# Sensors.net
KiCad netlist of a schematic drawn in Altium Designer
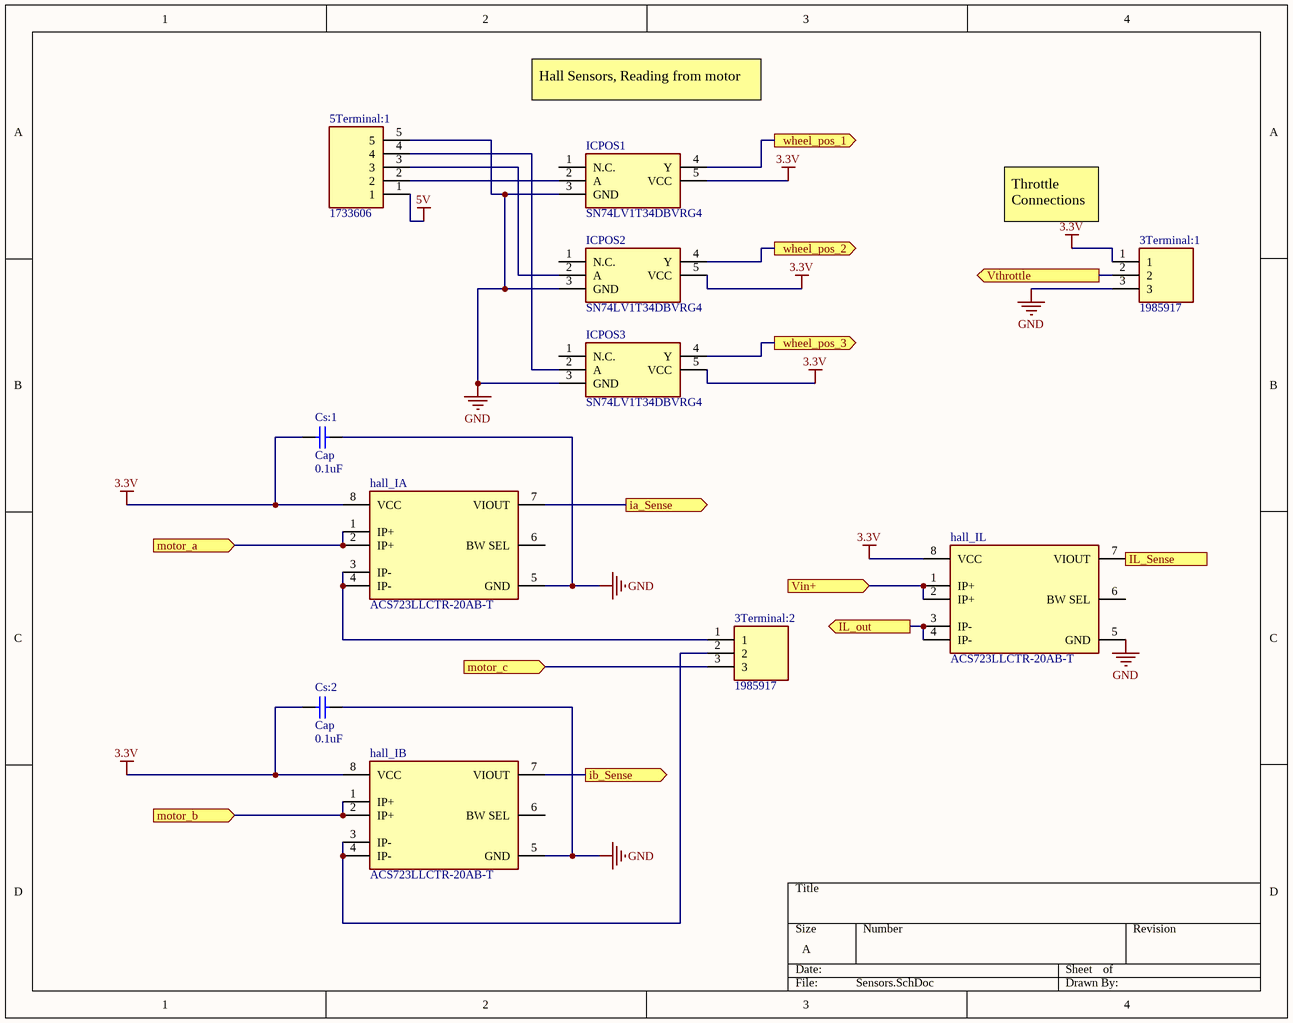
[diagram p0: Sensors.SchDoc]

(export (version "E")
  (design (tool "Eeschema 10.0.6"))
  (components
    (comp (ref "3Terminal:1")
      (value "1985917")
      (footprint "1985917")
      (description "Connector")
      (fields (field (name "MOUSER PART NUMBER") "651-1985917"))
      (libsource (lib "*") (part "1985917"))
    )
    (comp (ref "3Terminal:2")
      (value "1985917")
      (footprint "1985917")
      (description "Connector")
      (fields (field (name "MOUSER PART NUMBER") "651-1985917"))
      (libsource (lib "*") (part "1985917"))
    )
    (comp (ref "5Terminal:1")
      (value "1733606")
      (footprint "1733606")
      (description "Connector")
      (fields (field (name "MOUSER PART NUMBER") "651-1733606"))
      (libsource (lib "*") (part "1733606"))
    )
    (comp (ref "Cs:1")
      (value "Cap")
      (footprint "RAD-0.3")
      (description "Capacitor")
      (fields (field (name "ALTIUM_VALUE") "0.1uF") (field (name "PUBLISHER") "Altium Limited"))
      (libsource (lib "Miscellaneous Devices") (part "Cap"))
    )
    (comp (ref "Cs:2")
      (value "Cap")
      (footprint "RAD-0.3")
      (description "Capacitor")
      (fields (field (name "ALTIUM_VALUE") "0.1uF") (field (name "PUBLISHER") "Altium Limited"))
      (libsource (lib "Miscellaneous Devices") (part "Cap"))
    )
    (comp (ref "hall_IA")
      (value "ACS723LLCTR-20AB-T")
      (footprint "FP-LC-8-IPC_C")
      (description "SENSOR CURRENT HALL 20A AC/DC")
      (libsource (lib "Altium Content Vault") (part "ec8154914af847fa3e50e077efa1aaf"))
    )
    (comp (ref "hall_IB")
      (value "ACS723LLCTR-20AB-T")
      (footprint "FP-LC-8-IPC_C")
      (description "SENSOR CURRENT HALL 20A AC/DC")
      (libsource (lib "Altium Content Vault") (part "ec8154914af847fa3e50e077efa1aaf"))
    )
    (comp (ref "hall_IL")
      (value "ACS723LLCTR-20AB-T")
      (footprint "FP-LC-8-IPC_C")
      (description "SENSOR CURRENT HALL 20A AC/DC")
      (libsource (lib "Altium Content Vault") (part "ec8154914af847fa3e50e077efa1aaf"))
    )
    (comp (ref "ICPOS1")
      (value "SN74LV1T34DBVRG4")
      (footprint "SOT95P280X145-5N")
      (description "Integrated Circuit")
      (fields (field (name "MOUSER PART NUMBER") "595-SN74LV1T34DBVRG4"))
      (libsource (lib "*") (part "SN74LV1T34DBVRG4"))
    )
    (comp (ref "ICPOS2")
      (value "SN74LV1T34DBVRG4")
      (footprint "SOT95P280X145-5N")
      (description "Integrated Circuit")
      (fields (field (name "MOUSER PART NUMBER") "595-SN74LV1T34DBVRG4"))
      (libsource (lib "*") (part "SN74LV1T34DBVRG4"))
    )
    (comp (ref "ICPOS3")
      (value "SN74LV1T34DBVRG4")
      (footprint "SOT95P280X145-5N")
      (description "Integrated Circuit")
      (fields (field (name "MOUSER PART NUMBER") "595-SN74LV1T34DBVRG4"))
      (libsource (lib "*") (part "SN74LV1T34DBVRG4"))
    )
  )
  (nets
    (net (code "1") (name "/IL_Sense") (class "Default")
      (node (ref "hall_IL") (pin "7") (pinfunction "VIOUT_7") (pintype "passive"))
    )
    (net (code "2") (name "/IL_out") (class "Default")
      (node (ref "hall_IL") (pin "3") (pinfunction "IP-_3") (pintype "passive"))
      (node (ref "hall_IL") (pin "4") (pinfunction "IP-_4") (pintype "passive"))
    )
    (net (code "3") (name "/Vin+") (class "Default")
      (node (ref "hall_IL") (pin "1") (pinfunction "IP+_1") (pintype "passive"))
      (node (ref "hall_IL") (pin "2") (pinfunction "IP+_2") (pintype "passive"))
    )
    (net (code "4") (name "/Vthrottle") (class "Default")
      (node (ref "3Terminal:1") (pin "2") (pinfunction "2_2") (pintype "passive"))
    )
    (net (code "5") (name "/ia_Sense") (class "Default")
      (node (ref "hall_IA") (pin "7") (pinfunction "VIOUT_7") (pintype "passive"))
    )
    (net (code "6") (name "/ib_Sense") (class "Default")
      (node (ref "hall_IB") (pin "7") (pinfunction "VIOUT_7") (pintype "passive"))
    )
    (net (code "7") (name "/motor_a") (class "Default")
      (node (ref "hall_IA") (pin "1") (pinfunction "IP+_1") (pintype "passive"))
      (node (ref "hall_IA") (pin "2") (pinfunction "IP+_2") (pintype "passive"))
    )
    (net (code "8") (name "/motor_b") (class "Default")
      (node (ref "hall_IB") (pin "1") (pinfunction "IP+_1") (pintype "passive"))
      (node (ref "hall_IB") (pin "2") (pinfunction "IP+_2") (pintype "passive"))
    )
    (net (code "9") (name "/motor_c") (class "Default")
      (node (ref "3Terminal:2") (pin "3") (pinfunction "3_3") (pintype "passive"))
    )
    (net (code "10") (name "/wheel_pos_1") (class "Default")
      (node (ref "ICPOS1") (pin "4") (pinfunction "Y_4") (pintype "passive"))
    )
    (net (code "11") (name "/wheel_pos_2") (class "Default")
      (node (ref "ICPOS2") (pin "4") (pinfunction "Y_4") (pintype "passive"))
    )
    (net (code "12") (name "/wheel_pos_3") (class "Default")
      (node (ref "ICPOS3") (pin "4") (pinfunction "Y_4") (pintype "passive"))
    )
    (net (code "13") (name "3.3V") (class "Default")
      (node (ref "3Terminal:1") (pin "1") (pinfunction "1_1") (pintype "passive"))
      (node (ref "Cs:1") (pin "1") (pinfunction "1_1") (pintype "passive"))
      (node (ref "Cs:2") (pin "1") (pinfunction "1_1") (pintype "passive"))
      (node (ref "ICPOS1") (pin "5") (pinfunction "VCC_5") (pintype "passive"))
      (node (ref "ICPOS2") (pin "5") (pinfunction "VCC_5") (pintype "passive"))
      (node (ref "ICPOS3") (pin "5") (pinfunction "VCC_5") (pintype "passive"))
      (node (ref "hall_IA") (pin "8") (pinfunction "VCC_8") (pintype "power_in"))
      (node (ref "hall_IB") (pin "8") (pinfunction "VCC_8") (pintype "power_in"))
      (node (ref "hall_IL") (pin "8") (pinfunction "VCC_8") (pintype "power_in"))
    )
    (net (code "14") (name "5V") (class "Default")
      (node (ref "5Terminal:1") (pin "1") (pinfunction "1_1") (pintype "passive"))
    )
    (net (code "15") (name "GND") (class "Default")
      (node (ref "3Terminal:1") (pin "3") (pinfunction "3_3") (pintype "passive"))
      (node (ref "5Terminal:1") (pin "5") (pinfunction "5_5") (pintype "passive"))
      (node (ref "Cs:1") (pin "2") (pinfunction "2_2") (pintype "passive"))
      (node (ref "Cs:2") (pin "2") (pinfunction "2_2") (pintype "passive"))
      (node (ref "ICPOS1") (pin "3") (pinfunction "GND_3") (pintype "passive"))
      (node (ref "ICPOS2") (pin "3") (pinfunction "GND_3") (pintype "passive"))
      (node (ref "ICPOS3") (pin "3") (pinfunction "GND_3") (pintype "passive"))
      (node (ref "hall_IA") (pin "5") (pinfunction "GND_5") (pintype "power_in"))
      (node (ref "hall_IB") (pin "5") (pinfunction "GND_5") (pintype "power_in"))
      (node (ref "hall_IL") (pin "5") (pinfunction "GND_5") (pintype "power_in"))
    )
    (net (code "16") (name "Net-(3Terminal:2-Pad1)") (class "Default")
      (node (ref "3Terminal:2") (pin "1") (pinfunction "1_1") (pintype "passive"))
      (node (ref "hall_IA") (pin "3") (pinfunction "IP-_3") (pintype "passive"))
      (node (ref "hall_IA") (pin "4") (pinfunction "IP-_4") (pintype "passive"))
    )
    (net (code "17") (name "Net-(3Terminal:2-Pad2)") (class "Default")
      (node (ref "3Terminal:2") (pin "2") (pinfunction "2_2") (pintype "passive"))
      (node (ref "hall_IB") (pin "3") (pinfunction "IP-_3") (pintype "passive"))
      (node (ref "hall_IB") (pin "4") (pinfunction "IP-_4") (pintype "passive"))
    )
    (net (code "18") (name "Net-(ICPOS1-A)") (class "Default")
      (node (ref "5Terminal:1") (pin "2") (pinfunction "2_2") (pintype "passive"))
      (node (ref "ICPOS1") (pin "2") (pinfunction "A_2") (pintype "passive"))
    )
    (net (code "19") (name "Net-(ICPOS2-A)") (class "Default")
      (node (ref "5Terminal:1") (pin "3") (pinfunction "3_3") (pintype "passive"))
      (node (ref "ICPOS2") (pin "2") (pinfunction "A_2") (pintype "passive"))
    )
    (net (code "20") (name "Net-(ICPOS3-A)") (class "Default")
      (node (ref "5Terminal:1") (pin "4") (pinfunction "4_4") (pintype "passive"))
      (node (ref "ICPOS3") (pin "2") (pinfunction "A_2") (pintype "passive"))
    )
    (net (code "21") (name "unconnected-(ICPOS1-N.C.-Pad1)") (class "Default")
      (node (ref "ICPOS1") (pin "1") (pinfunction "N.C._1") (pintype "passive"))
    )
    (net (code "22") (name "unconnected-(ICPOS2-N.C.-Pad1)") (class "Default")
      (node (ref "ICPOS2") (pin "1") (pinfunction "N.C._1") (pintype "passive"))
    )
    (net (code "23") (name "unconnected-(ICPOS3-N.C.-Pad1)") (class "Default")
      (node (ref "ICPOS3") (pin "1") (pinfunction "N.C._1") (pintype "passive"))
    )
    (net (code "24") (name "unconnected-(hall_IA-BW_SEL-Pad6)") (class "Default")
      (node (ref "hall_IA") (pin "6") (pinfunction "BW_SEL_6") (pintype "power_in"))
    )
    (net (code "25") (name "unconnected-(hall_IB-BW_SEL-Pad6)") (class "Default")
      (node (ref "hall_IB") (pin "6") (pinfunction "BW_SEL_6") (pintype "power_in"))
    )
    (net (code "26") (name "unconnected-(hall_IL-BW_SEL-Pad6)") (class "Default")
      (node (ref "hall_IL") (pin "6") (pinfunction "BW_SEL_6") (pintype "power_in"))
    )
  )
)
